# res15_nrf905.net
KiCad netlist of a schematic drawn in EAGLE
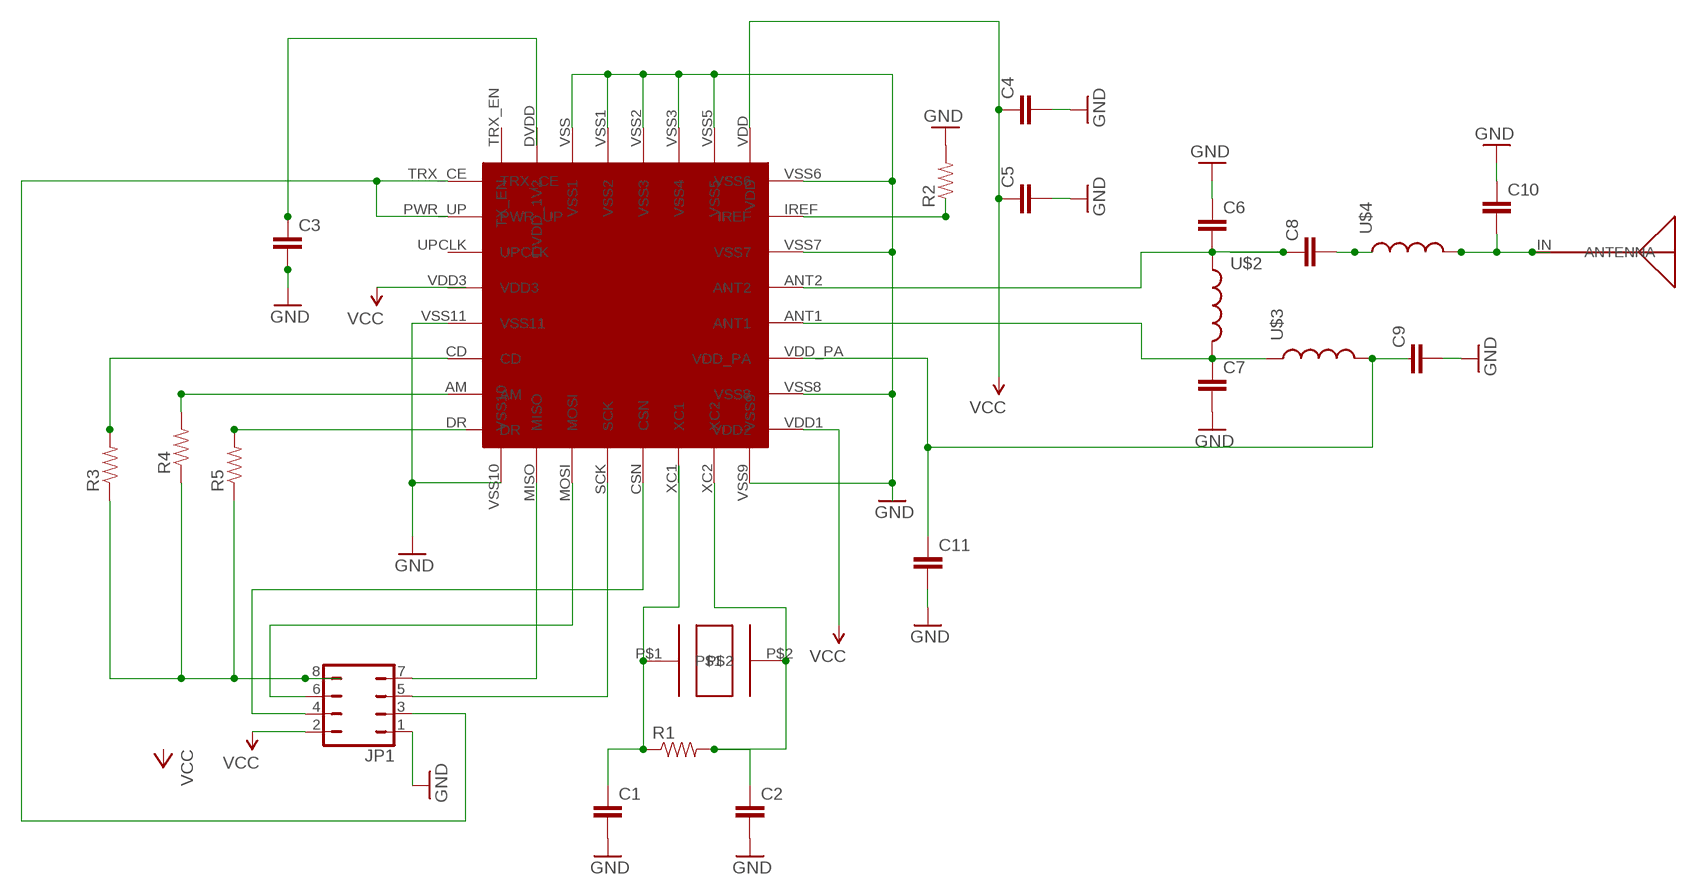
[diagram p0: schematic, sheet 1]

(export (version "E")
  (design (tool "Eeschema 10.0.6"))
  (components
    (comp (ref "C1")
      (value "CAP0402-CAP")
      (footprint "eagle-import:0402-CAP")
      (libsource (lib "eagle-import") (part "CAP0402-CAP"))
    )
    (comp (ref "C2")
      (value "CAP0402-CAP")
      (footprint "eagle-import:0402-CAP")
      (libsource (lib "eagle-import") (part "CAP0402-CAP"))
    )
    (comp (ref "C3")
      (value "CAP0402-CAP")
      (footprint "eagle-import:0402-CAP")
      (libsource (lib "eagle-import") (part "CAP0402-CAP"))
    )
    (comp (ref "C4")
      (value "CAP0402-CAP")
      (footprint "eagle-import:0402-CAP")
      (libsource (lib "eagle-import") (part "CAP0402-CAP"))
    )
    (comp (ref "C5")
      (value "CAP0402-CAP")
      (footprint "eagle-import:0402-CAP")
      (libsource (lib "eagle-import") (part "CAP0402-CAP"))
    )
    (comp (ref "C6")
      (value "CAP0402-CAP")
      (footprint "eagle-import:0402-CAP")
      (libsource (lib "eagle-import") (part "CAP0402-CAP"))
    )
    (comp (ref "C7")
      (value "CAP0402-CAP")
      (footprint "eagle-import:0402-CAP")
      (libsource (lib "eagle-import") (part "CAP0402-CAP"))
    )
    (comp (ref "C8")
      (value "CAP0402-CAP")
      (footprint "eagle-import:0402-CAP")
      (libsource (lib "eagle-import") (part "CAP0402-CAP"))
    )
    (comp (ref "C9")
      (value "CAP0402-CAP")
      (footprint "eagle-import:0402-CAP")
      (libsource (lib "eagle-import") (part "CAP0402-CAP"))
    )
    (comp (ref "C10")
      (value "CAP0402-CAP")
      (footprint "eagle-import:0402-CAP")
      (libsource (lib "eagle-import") (part "CAP0402-CAP"))
    )
    (comp (ref "C11")
      (value "CAP0402-CAP")
      (footprint "eagle-import:0402-CAP")
      (libsource (lib "eagle-import") (part "CAP0402-CAP"))
    )
    (comp (ref "JP1")
      (value "JP4Q")
      (footprint "eagle-import:JP4Q")
      (libsource (lib "eagle-import") (part "JP4Q"))
    )
    (comp (ref "R1")
      (value "RESISTOR0402-RES")
      (footprint "eagle-import:0402-RES")
      (libsource (lib "eagle-import") (part "RESISTOR0402-RES"))
    )
    (comp (ref "R2")
      (value "RESISTOR0603-RES")
      (footprint "eagle-import:0603-RES")
      (libsource (lib "eagle-import") (part "RESISTOR0603-RES"))
    )
    (comp (ref "R3")
      (value "RESISTOR0603-RES")
      (footprint "eagle-import:0603-RES")
      (libsource (lib "eagle-import") (part "RESISTOR0603-RES"))
    )
    (comp (ref "R4")
      (value "RESISTOR0603-RES")
      (footprint "eagle-import:0603-RES")
      (libsource (lib "eagle-import") (part "RESISTOR0603-RES"))
    )
    (comp (ref "R5")
      (value "RESISTOR0603-RES")
      (footprint "eagle-import:0603-RES")
      (libsource (lib "eagle-import") (part "RESISTOR0603-RES"))
    )
    (comp (ref "U$1")
      (value "NRF905")
      (footprint "eagle-import:NRF905")
      (libsource (lib "eagle-import") (part "NRF905"))
    )
    (comp (ref "U$2")
      (value "INDUCTOR0603")
      (footprint "eagle-import:0603")
      (libsource (lib "eagle-import") (part "INDUCTOR0603"))
    )
    (comp (ref "U$3")
      (value "INDUCTOR0603")
      (footprint "eagle-import:0603")
      (libsource (lib "eagle-import") (part "INDUCTOR0603"))
    )
    (comp (ref "U$4")
      (value "INDUCTOR0603")
      (footprint "eagle-import:0603")
      (libsource (lib "eagle-import") (part "INDUCTOR0603"))
    )
    (comp (ref "U$5")
      (value "WURTH-7488910092")
      (footprint "eagle-import:WURTH-7488910092")
      (libsource (lib "eagle-import") (part "WURTH-7488910092"))
    )
    (comp (ref "U$6")
      (value "HC46X")
      (footprint "eagle-import:HC46X")
      (libsource (lib "eagle-import") (part "HC46X"))
    )
  )
  (nets
    (net (code "1") (name "/DR") (class "Default")
      (node (ref "U$1") (pin "DR") (pinfunction "DR_DR") (pintype "power_in"))
    )
    (net (code "2") (name "/VDD3") (class "Default")
      (node (ref "U$1") (pin "VDD3") (pinfunction "VDD3_VDD3") (pintype "power_in"))
    )
    (net (code "3") (name "GND") (class "Default")
      (node (ref "C1") (pin "2") (pinfunction "2_2") (pintype "passive"))
      (node (ref "C10") (pin "1") (pinfunction "1_1") (pintype "passive"))
      (node (ref "C11") (pin "2") (pinfunction "2_2") (pintype "passive"))
      (node (ref "C2") (pin "2") (pinfunction "2_2") (pintype "passive"))
      (node (ref "C3") (pin "2") (pinfunction "2_2") (pintype "passive"))
      (node (ref "C4") (pin "2") (pinfunction "2_2") (pintype "passive"))
      (node (ref "C5") (pin "2") (pinfunction "2_2") (pintype "passive"))
      (node (ref "C6") (pin "1") (pinfunction "1_1") (pintype "passive"))
      (node (ref "C7") (pin "2") (pinfunction "2_2") (pintype "passive"))
      (node (ref "C9") (pin "2") (pinfunction "2_2") (pintype "passive"))
      (node (ref "JP1") (pin "1") (pinfunction "1_1") (pintype "passive"))
      (node (ref "R2") (pin "2") (pinfunction "2_2") (pintype "passive"))
      (node (ref "U$1") (pin "VSS") (pinfunction "VSS1_VSS") (pintype "power_in"))
      (node (ref "U$1") (pin "VSS1") (pinfunction "VSS2_VSS1") (pintype "power_in"))
      (node (ref "U$1") (pin "VSS10") (pinfunction "VSS10_VSS10") (pintype "bidirectional"))
      (node (ref "U$1") (pin "VSS11") (pinfunction "VSS11_VSS11") (pintype "power_in"))
      (node (ref "U$1") (pin "VSS2") (pinfunction "VSS3_VSS2") (pintype "power_in"))
      (node (ref "U$1") (pin "VSS3") (pinfunction "VSS4_VSS3") (pintype "bidirectional"))
      (node (ref "U$1") (pin "VSS5") (pinfunction "VSS5_VSS5") (pintype "power_in"))
      (node (ref "U$1") (pin "VSS6") (pinfunction "VSS6_VSS6") (pintype "power_in"))
      (node (ref "U$1") (pin "VSS7") (pinfunction "VSS7_VSS7") (pintype "power_in"))
      (node (ref "U$1") (pin "VSS8") (pinfunction "VSS8_VSS8") (pintype "power_in"))
      (node (ref "U$1") (pin "VSS9") (pinfunction "VSS9_VSS9") (pintype "power_in"))
    )
    (net (code "4") (name "Net-(C1-Pad1)") (class "Default")
      (node (ref "C1") (pin "1") (pinfunction "1_1") (pintype "passive"))
      (node (ref "R1") (pin "1") (pinfunction "1_1") (pintype "passive"))
      (node (ref "U$6") (pin "P$1") (pinfunction "P$1_P$1") (pintype "bidirectional"))
    )
    (net (code "5") (name "Net-(C2-Pad1)") (class "Default")
      (node (ref "C2") (pin "1") (pinfunction "1_1") (pintype "passive"))
      (node (ref "R1") (pin "2") (pinfunction "2_2") (pintype "passive"))
      (node (ref "U$1") (pin "XC2") (pinfunction "XC2_XC2") (pintype "input"))
      (node (ref "U$6") (pin "P$2") (pinfunction "P$2_P$2") (pintype "bidirectional"))
    )
    (net (code "6") (name "Net-(C6-Pad2)") (class "Default")
      (node (ref "C6") (pin "2") (pinfunction "2_2") (pintype "passive"))
      (node (ref "C8") (pin "1") (pinfunction "1_1") (pintype "passive"))
      (node (ref "U$1") (pin "ANT2") (pinfunction "ANT2_ANT2") (pintype "output"))
      (node (ref "U$2") (pin "1") (pinfunction "1_1") (pintype "passive"))
    )
    (net (code "7") (name "Net-(C7-Pad1)") (class "Default")
      (node (ref "C7") (pin "1") (pinfunction "1_1") (pintype "passive"))
      (node (ref "U$1") (pin "ANT1") (pinfunction "ANT1_ANT1") (pintype "output"))
      (node (ref "U$2") (pin "2") (pinfunction "2_2") (pintype "passive"))
      (node (ref "U$3") (pin "1") (pinfunction "1_1") (pintype "passive"))
    )
    (net (code "8") (name "Net-(C8-Pad2)") (class "Default")
      (node (ref "C8") (pin "2") (pinfunction "2_2") (pintype "passive"))
      (node (ref "U$4") (pin "1") (pinfunction "1_1") (pintype "passive"))
    )
    (net (code "9") (name "Net-(C11-Pad1)") (class "Default")
      (node (ref "C11") (pin "1") (pinfunction "1_1") (pintype "passive"))
      (node (ref "U$1") (pin "VDD_PA") (pinfunction "VDD_PA_VDD_PA") (pintype "output"))
      (node (ref "U$3") (pin "2") (pinfunction "2_2") (pintype "passive"))
    )
    (net (code "10") (name "Net-(JP1-Pad3)") (class "Default")
      (node (ref "JP1") (pin "3") (pinfunction "3_3") (pintype "passive"))
      (node (ref "U$1") (pin "PWR_UP") (pinfunction "PWR_UP_PWR_UP") (pintype "input"))
      (node (ref "U$1") (pin "TRX_CE") (pinfunction "TRX_CE_TRX_CE") (pintype "bidirectional"))
    )
    (net (code "11") (name "Net-(JP1-Pad4)") (class "Default")
      (node (ref "JP1") (pin "4") (pinfunction "4_4") (pintype "passive"))
      (node (ref "U$1") (pin "CSN") (pinfunction "CSN_CSN") (pintype "bidirectional"))
    )
    (net (code "12") (name "Net-(JP1-Pad5)") (class "Default")
      (node (ref "JP1") (pin "5") (pinfunction "5_5") (pintype "passive"))
      (node (ref "U$1") (pin "SCK") (pinfunction "SCK_SCK") (pintype "bidirectional"))
    )
    (net (code "13") (name "Net-(JP1-Pad6)") (class "Default")
      (node (ref "JP1") (pin "6") (pinfunction "6_6") (pintype "passive"))
      (node (ref "U$1") (pin "MOSI") (pinfunction "MOSI_MOSI") (pintype "bidirectional"))
    )
    (net (code "14") (name "Net-(JP1-Pad7)") (class "Default")
      (node (ref "JP1") (pin "7") (pinfunction "7_7") (pintype "passive"))
      (node (ref "U$1") (pin "MISO") (pinfunction "MISO_MISO") (pintype "bidirectional"))
    )
    (net (code "15") (name "Net-(JP1-Pad8)") (class "Default")
      (node (ref "JP1") (pin "8") (pinfunction "8_8") (pintype "passive"))
      (node (ref "R3") (pin "1") (pinfunction "1_1") (pintype "passive"))
      (node (ref "R4") (pin "1") (pinfunction "1_1") (pintype "passive"))
      (node (ref "R5") (pin "1") (pinfunction "1_1") (pintype "passive"))
    )
    (net (code "16") (name "Net-(R2-Pad1)") (class "Default")
      (node (ref "R2") (pin "1") (pinfunction "1_1") (pintype "passive"))
      (node (ref "U$1") (pin "IREF") (pinfunction "IREF_IREF") (pintype "bidirectional"))
    )
    (net (code "17") (name "Net-(R3-Pad2)") (class "Default")
      (node (ref "R3") (pin "2") (pinfunction "2_2") (pintype "passive"))
      (node (ref "U$1") (pin "CD") (pinfunction "CD_CD") (pintype "bidirectional"))
    )
    (net (code "18") (name "Net-(R4-Pad2)") (class "Default")
      (node (ref "R4") (pin "2") (pinfunction "2_2") (pintype "passive"))
      (node (ref "U$1") (pin "AM") (pinfunction "AM_AM") (pintype "bidirectional"))
    )
    (net (code "19") (name "Net-(U$5-ANTENNA)") (class "Default")
      (node (ref "C10") (pin "2") (pinfunction "2_2") (pintype "passive"))
      (node (ref "U$4") (pin "2") (pinfunction "2_2") (pintype "passive"))
      (node (ref "U$5") (pin "IN") (pinfunction "ANTENNA_IN") (pintype "input"))
    )
    (net (code "20") (name "VCC") (class "Default")
      (node (ref "C4") (pin "1") (pinfunction "1_1") (pintype "passive"))
      (node (ref "C5") (pin "1") (pinfunction "1_1") (pintype "passive"))
      (node (ref "JP1") (pin "2") (pinfunction "2_2") (pintype "passive"))
      (node (ref "U$1") (pin "VDD") (pinfunction "VDD_VDD") (pintype "power_in"))
      (node (ref "U$1") (pin "VDD1") (pinfunction "VDD2_VDD1") (pintype "power_in"))
    )
    (net (code "21") (name "unconnected-(C3-Pad1)") (class "Default")
      (node (ref "C3") (pin "1") (pinfunction "1_1") (pintype "passive"))
    )
    (net (code "22") (name "unconnected-(C9-Pad1)") (class "Default")
      (node (ref "C9") (pin "1") (pinfunction "1_1") (pintype "passive"))
    )
    (net (code "23") (name "unconnected-(R5-Pad2)") (class "Default")
      (node (ref "R5") (pin "2") (pinfunction "2_2") (pintype "passive"))
    )
    (net (code "24") (name "unconnected-(U$1-DVDD_1V2-PadDVDD)") (class "Default")
      (node (ref "U$1") (pin "DVDD") (pinfunction "DVDD_1V2_DVDD") (pintype "bidirectional"))
    )
    (net (code "25") (name "unconnected-(U$1-PadUPCLK)") (class "Default")
      (node (ref "U$1") (pin "UPCLK") (pinfunction "UPCLK_UPCLK") (pintype "input"))
    )
    (net (code "26") (name "unconnected-(U$1-PadXC1)") (class "Default")
      (node (ref "U$1") (pin "XC1") (pinfunction "XC1_XC1") (pintype "input"))
    )
    (net (code "27") (name "unconnected-(U$1-TX_EN-PadTRX_EN)") (class "Default")
      (node (ref "U$1") (pin "TRX_EN") (pinfunction "TX_EN_TRX_EN") (pintype "bidirectional"))
    )
  )
)
